# pwmTransmitter.net
KiCad netlist of a schematic drawn in EAGLE
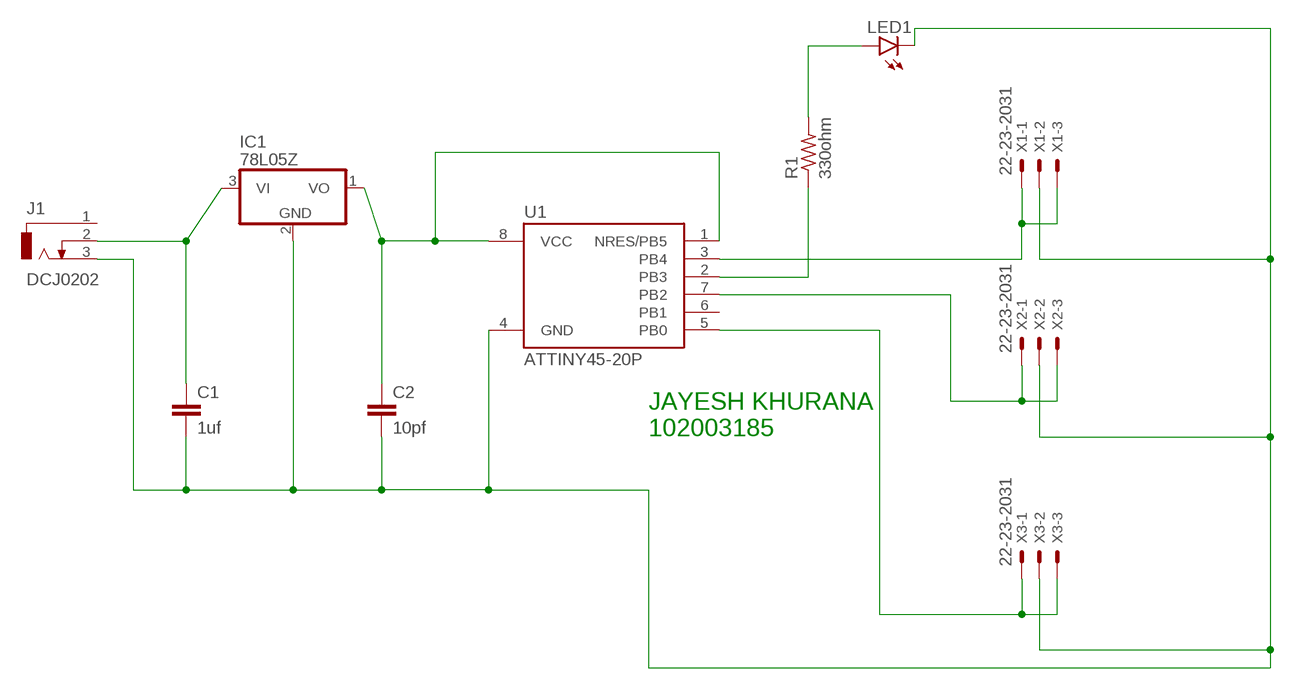
[diagram p0: schematic, sheet 1]

(export (version "E")
  (design (tool "Eeschema 10.0.6"))
  (components
    (comp (ref "C1")
      (value "1uf")
      (footprint "eagle-import:C2.5-2")
      (libsource (lib "eagle-import") (part "C2.5/2"))
    )
    (comp (ref "C2")
      (value "10pf")
      (footprint "eagle-import:C2.5-2")
      (libsource (lib "eagle-import") (part "C2.5/2"))
    )
    (comp (ref "IC1")
      (value "78L05Z")
      (footprint "eagle-import:TO92")
      (libsource (lib "eagle-import") (part "78ZL05"))
    )
    (comp (ref "J1")
      (value "DCJ0202")
      (footprint "eagle-import:DCJ0202")
      (libsource (lib "eagle-import") (part "DCJ0202"))
    )
    (comp (ref "LED1")
      (value "LED3MM")
      (footprint "eagle-import:LED3MM")
      (libsource (lib "eagle-import") (part "LED3MM"))
    )
    (comp (ref "R1")
      (value "330ohm")
      (footprint "eagle-import:0207_10")
      (libsource (lib "eagle-import") (part "R-US_0207/10"))
    )
    (comp (ref "U1")
      (value "ATTINY45-20P")
      (footprint "eagle-import:PDIP08_300MIL")
      (libsource (lib "eagle-import") (part "ATTINY45P-20"))
    )
    (comp (ref "X1")
      (value "22-23-2031")
      (footprint "eagle-import:22-23-2031")
      (fields (field (name "MF") "MOLEX"))
      (libsource (lib "eagle-import") (part "22-23-2031"))
    )
    (comp (ref "X2")
      (value "22-23-2031")
      (footprint "eagle-import:22-23-2031")
      (fields (field (name "MF") "MOLEX"))
      (libsource (lib "eagle-import") (part "22-23-2031"))
    )
    (comp (ref "X3")
      (value "22-23-2031")
      (footprint "eagle-import:22-23-2031")
      (fields (field (name "MF") "MOLEX"))
      (libsource (lib "eagle-import") (part "22-23-2031"))
    )
  )
  (nets
    (net (code "1") (name "Net-(IC1-GND)") (class "Default")
      (node (ref "C1") (pin "2") (pinfunction "2_2") (pintype "passive"))
      (node (ref "C2") (pin "2") (pinfunction "2_2") (pintype "passive"))
      (node (ref "IC1") (pin "2") (pinfunction "GND_2") (pintype "passive"))
      (node (ref "J1") (pin "3") (pinfunction "3_3") (pintype "passive"))
      (node (ref "LED1") (pin "K") (pinfunction "C_K") (pintype "passive"))
      (node (ref "U1") (pin "4") (pinfunction "GND_4") (pintype "power_in"))
      (node (ref "X1") (pin "2") (pinfunction "S_2") (pintype "passive"))
      (node (ref "X2") (pin "2") (pinfunction "S_2") (pintype "passive"))
      (node (ref "X3") (pin "2") (pinfunction "S_2") (pintype "passive"))
    )
    (net (code "2") (name "Net-(IC1-VI)") (class "Default")
      (node (ref "C1") (pin "1") (pinfunction "1_1") (pintype "passive"))
      (node (ref "IC1") (pin "3") (pinfunction "VI_3") (pintype "input"))
      (node (ref "J1") (pin "2") (pinfunction "2_2") (pintype "passive"))
    )
    (net (code "3") (name "Net-(IC1-VO)") (class "Default")
      (node (ref "C2") (pin "1") (pinfunction "1_1") (pintype "passive"))
      (node (ref "IC1") (pin "1") (pinfunction "VO_1") (pintype "passive"))
      (node (ref "U1") (pin "1") (pinfunction "NRES/PB5_1") (pintype "bidirectional"))
      (node (ref "U1") (pin "8") (pinfunction "VCC_8") (pintype "power_in"))
    )
    (net (code "4") (name "Net-(LED1-PadA)") (class "Default")
      (node (ref "LED1") (pin "A") (pinfunction "A_A") (pintype "passive"))
      (node (ref "R1") (pin "2") (pinfunction "2_2") (pintype "passive"))
    )
    (net (code "5") (name "Net-(U1-PB0)") (class "Default")
      (node (ref "U1") (pin "5") (pinfunction "PB0_5") (pintype "bidirectional"))
      (node (ref "X3") (pin "1") (pinfunction "S_1") (pintype "passive"))
      (node (ref "X3") (pin "3") (pinfunction "S_3") (pintype "passive"))
    )
    (net (code "6") (name "Net-(U1-PB2)") (class "Default")
      (node (ref "U1") (pin "7") (pinfunction "PB2_7") (pintype "bidirectional"))
      (node (ref "X2") (pin "1") (pinfunction "S_1") (pintype "passive"))
      (node (ref "X2") (pin "3") (pinfunction "S_3") (pintype "passive"))
    )
    (net (code "7") (name "Net-(U1-PB3)") (class "Default")
      (node (ref "R1") (pin "1") (pinfunction "1_1") (pintype "passive"))
      (node (ref "U1") (pin "2") (pinfunction "PB3_2") (pintype "bidirectional"))
    )
    (net (code "8") (name "Net-(U1-PB4)") (class "Default")
      (node (ref "U1") (pin "3") (pinfunction "PB4_3") (pintype "bidirectional"))
      (node (ref "X1") (pin "1") (pinfunction "S_1") (pintype "passive"))
      (node (ref "X1") (pin "3") (pinfunction "S_3") (pintype "passive"))
    )
    (net (code "9") (name "unconnected-(J1-Pad1)") (class "Default")
      (node (ref "J1") (pin "1") (pinfunction "1_1") (pintype "passive"))
    )
    (net (code "10") (name "unconnected-(U1-PB1-Pad6)") (class "Default")
      (node (ref "U1") (pin "6") (pinfunction "PB1_6") (pintype "bidirectional"))
    )
  )
)
